# power_measure.net
KiCad netlist of a schematic drawn in Altium Designer
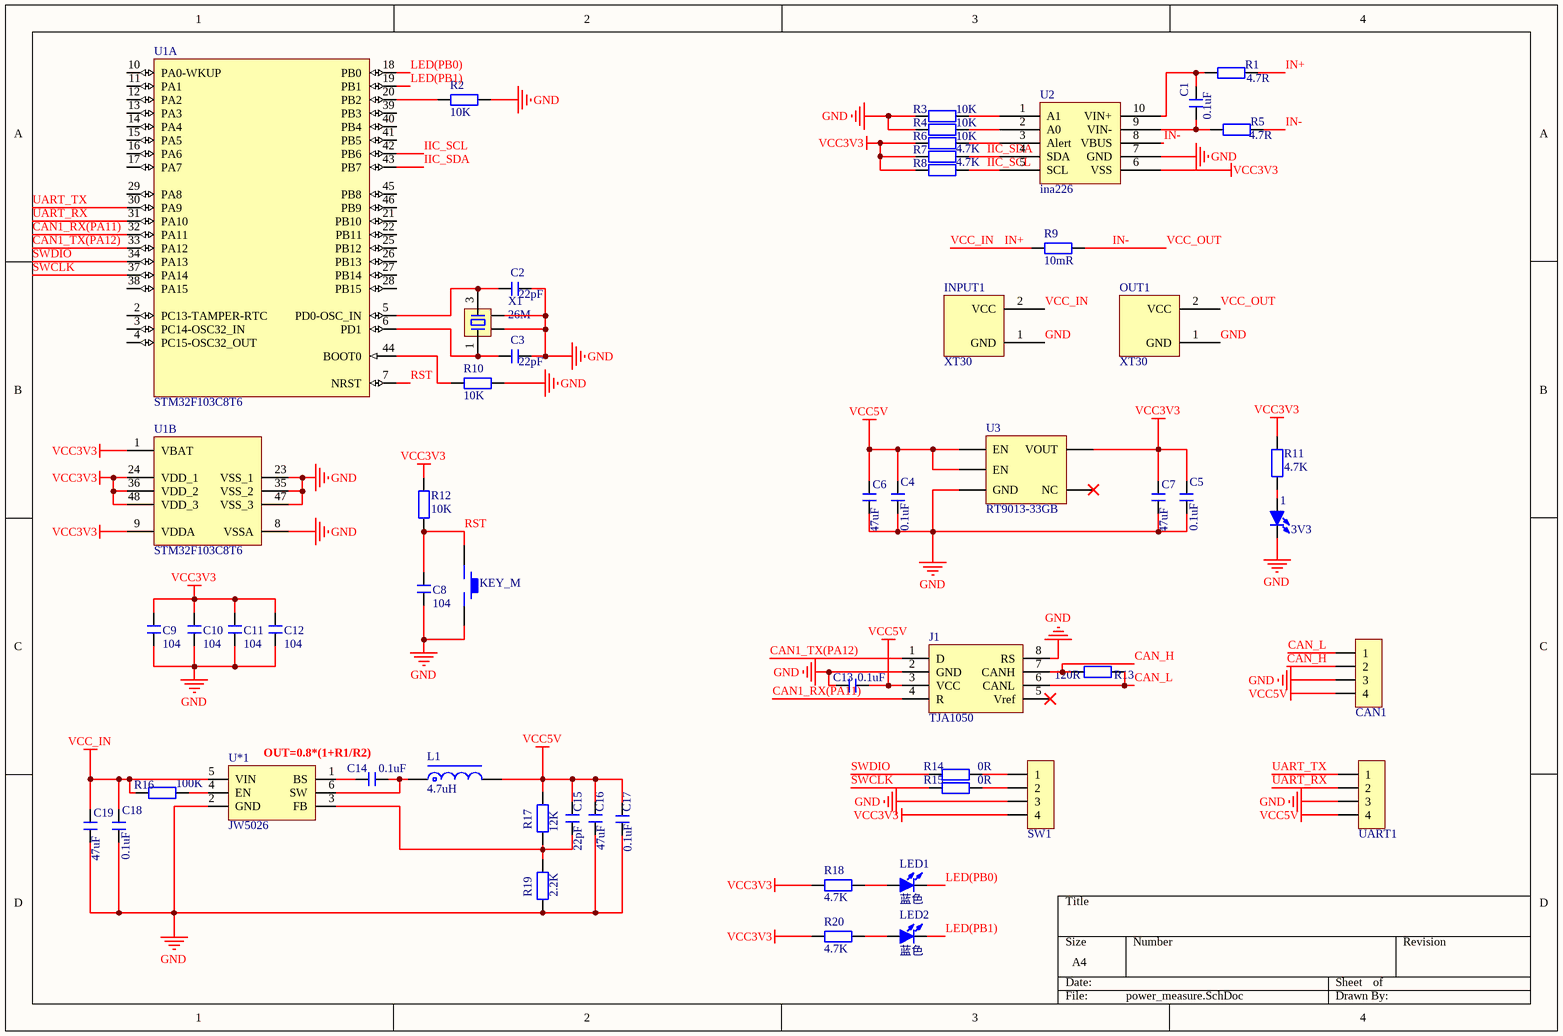
[diagram p0: power_measure.SchDoc]

(export (version "E")
  (design (tool "Eeschema 10.0.6"))
  (components
    (comp (ref "1")
      (value "3V3")
      (footprint "LED 0805R")
      (description "贴片LED")
      (libsource (lib "0.3 - LED发光二极管") (part "LED-SMD"))
    )
    (comp (ref "C1")
      (value "0.1uF")
      (footprint "C 0603_L")
      (description "贴片电容")
      (libsource (lib "0.1 - 电阻-电容-电感") (part "C"))
    )
    (comp (ref "C2")
      (value "22pF")
      (footprint "C 0603_L")
      (description "贴片电容")
      (libsource (lib "0.1 - 电阻-电容-电感") (part "C"))
    )
    (comp (ref "C3")
      (value "22pF")
      (footprint "C 0603_L")
      (description "贴片电容")
      (libsource (lib "0.1 - 电阻-电容-电感") (part "C"))
    )
    (comp (ref "C4")
      (value "0.1uF")
      (footprint "C 0805_L")
      (description "贴片电容")
      (libsource (lib "0.1 - 电阻-电容-电感") (part "C"))
    )
    (comp (ref "C5")
      (value "0.1uF")
      (footprint "C 0805_L")
      (description "贴片电容")
      (libsource (lib "0.1 - 电阻-电容-电感") (part "C"))
    )
    (comp (ref "C6")
      (value "47uF")
      (footprint "C 0805_L")
      (description "贴片电容")
      (libsource (lib "0.1 - 电阻-电容-电感") (part "C"))
    )
    (comp (ref "C7")
      (value "47uF")
      (footprint "C 0805_L")
      (description "贴片电容")
      (libsource (lib "0.1 - 电阻-电容-电感") (part "C"))
    )
    (comp (ref "C8")
      (value "104")
      (footprint "C 0603_L")
      (description "贴片电容")
      (libsource (lib "0.1 - 电阻-电容-电感") (part "C"))
    )
    (comp (ref "C9")
      (value "104")
      (footprint "C 0603_L")
      (description "贴片电容")
      (libsource (lib "0.1 - 电阻-电容-电感") (part "C"))
    )
    (comp (ref "C10")
      (value "104")
      (footprint "C 0603_L")
      (description "贴片电容")
      (libsource (lib "0.1 - 电阻-电容-电感") (part "C"))
    )
    (comp (ref "C11")
      (value "104")
      (footprint "C 0603_L")
      (description "贴片电容")
      (libsource (lib "0.1 - 电阻-电容-电感") (part "C"))
    )
    (comp (ref "C12")
      (value "104")
      (footprint "C 0603_L")
      (description "贴片电容")
      (libsource (lib "0.1 - 电阻-电容-电感") (part "C"))
    )
    (comp (ref "C13")
      (value "0.1uF")
      (footprint "C 0603_L")
      (description "贴片电容")
      (libsource (lib "0.1 - 电阻-电容-电感") (part "C"))
    )
    (comp (ref "C14")
      (value "0.1uF")
      (footprint "C 0603_L")
      (description "贴片电容")
      (libsource (lib "0.1 - 电阻-电容-电感") (part "C"))
    )
    (comp (ref "C15")
      (value "22pF")
      (footprint "C 0603_L")
      (description "贴片电容")
      (libsource (lib "0.1 - 电阻-电容-电感") (part "C"))
    )
    (comp (ref "C16")
      (value "47uF")
      (footprint "C 0805_L")
      (description "贴片电容")
      (libsource (lib "0.1 - 电阻-电容-电感") (part "C"))
    )
    (comp (ref "C17")
      (value "0.1uF")
      (footprint "C 0805_L")
      (description "贴片电容")
      (libsource (lib "0.1 - 电阻-电容-电感") (part "C"))
    )
    (comp (ref "C18")
      (value "0.1uF")
      (footprint "C 0805_L")
      (description "贴片电容")
      (libsource (lib "0.1 - 电阻-电容-电感") (part "C"))
    )
    (comp (ref "C19")
      (value "47uF")
      (footprint "C 0805_L")
      (description "贴片电容")
      (libsource (lib "0.1 - 电阻-电容-电感") (part "C"))
    )
    (comp (ref "CAN1")
      (value "HDR-1X4")
      (footprint "MX 1.25-WS-4P")
      (description "4P接插件")
      (libsource (lib "5.0 - 接插件-脚距1.25") (part "Header 4"))
    )
    (comp (ref "INPUT1")
      (value "XT30")
      (footprint "mx_pcb_library:XT30PW-M")
      (libsource (lib "mx_pcb_library") (part "XT30"))
    )
    (comp (ref "J1")
      (value "TJA1050")
      (footprint "mx_pcb_library:SOIC-8_150mil")
      (description "CAN芯片")
      (libsource (lib "mx_pcb_library") (part "TJA1050"))
    )
    (comp (ref "L1")
      (value "4.7uH")
      (footprint "CD53")
      (description "CD系列贴片线绕功率电感")
      (libsource (lib "0.1 - 电阻-电容-电感") (part "L-SMD"))
    )
    (comp (ref "LED1")
      (value "蓝色")
      (footprint "LED 0805B")
      (description "贴片LED")
      (libsource (lib "0.3 - LED发光二极管") (part "LED-SMD"))
    )
    (comp (ref "LED2")
      (value "蓝色")
      (footprint "LED 0805B")
      (description "贴片LED")
      (libsource (lib "0.3 - LED发光二极管") (part "LED-SMD"))
    )
    (comp (ref "OUT1")
      (value "XT30")
      (footprint "mx_pcb_library:XT30PW-F")
      (libsource (lib "mx_pcb_library") (part "XT30"))
    )
    (comp (ref "R1")
      (value "4.7R")
      (footprint "R 0603_L")
      (description "贴片电阻")
      (libsource (lib "0.1 - 电阻-电容-电感") (part "R"))
    )
    (comp (ref "R2")
      (value "10K")
      (footprint "R 0603_L")
      (description "贴片电阻")
      (libsource (lib "0.1 - 电阻-电容-电感") (part "R"))
    )
    (comp (ref "R3")
      (value "10K")
      (footprint "R 0603_L")
      (description "贴片电阻")
      (libsource (lib "0.1 - 电阻-电容-电感") (part "R"))
    )
    (comp (ref "R4")
      (value "10K")
      (footprint "R 0603_L")
      (description "贴片电阻")
      (libsource (lib "0.1 - 电阻-电容-电感") (part "R"))
    )
    (comp (ref "R5")
      (value "4.7R")
      (footprint "R 0603_L")
      (description "贴片电阻")
      (libsource (lib "0.1 - 电阻-电容-电感") (part "R"))
    )
    (comp (ref "R6")
      (value "10K")
      (footprint "R 0603_L")
      (description "贴片电阻")
      (libsource (lib "0.1 - 电阻-电容-电感") (part "R"))
    )
    (comp (ref "R7")
      (value "4.7K")
      (footprint "R 0603_L")
      (description "贴片电阻")
      (libsource (lib "0.1 - 电阻-电容-电感") (part "R"))
    )
    (comp (ref "R8")
      (value "4.7K")
      (footprint "R 0603_L")
      (description "贴片电阻")
      (libsource (lib "0.1 - 电阻-电容-电感") (part "R"))
    )
    (comp (ref "R9")
      (value "10mR")
      (footprint "R 2512_M")
      (description "贴片电阻")
      (libsource (lib "0.1 - 电阻-电容-电感") (part "R"))
    )
    (comp (ref "R10")
      (value "10K")
      (footprint "R 0603_L")
      (description "贴片电阻")
      (libsource (lib "0.1 - 电阻-电容-电感") (part "R"))
    )
    (comp (ref "R11")
      (value "4.7K")
      (footprint "R 0603_L")
      (description "贴片电阻")
      (libsource (lib "0.1 - 电阻-电容-电感") (part "R"))
    )
    (comp (ref "R12")
      (value "10K")
      (footprint "R 0603_L")
      (description "贴片电阻")
      (libsource (lib "0.1 - 电阻-电容-电感") (part "R"))
    )
    (comp (ref "R13")
      (value "120R")
      (footprint "R 0603_L")
      (description "贴片电阻")
      (libsource (lib "0.1 - 电阻-电容-电感") (part "R"))
    )
    (comp (ref "R14")
      (value "0R")
      (footprint "R 0603_L")
      (description "贴片电阻")
      (libsource (lib "0.1 - 电阻-电容-电感") (part "R"))
    )
    (comp (ref "R15")
      (value "0R")
      (footprint "R 0603_L")
      (description "贴片电阻")
      (libsource (lib "0.1 - 电阻-电容-电感") (part "R"))
    )
    (comp (ref "R16")
      (value "100K")
      (footprint "R 0603_L")
      (description "贴片电阻")
      (libsource (lib "0.1 - 电阻-电容-电感") (part "R"))
    )
    (comp (ref "R17")
      (value "12K")
      (footprint "R 0603_L")
      (description "贴片电阻")
      (libsource (lib "0.1 - 电阻-电容-电感") (part "R"))
    )
    (comp (ref "R18")
      (value "4.7K")
      (footprint "R 0603_L")
      (description "贴片电阻")
      (libsource (lib "0.1 - 电阻-电容-电感") (part "R"))
    )
    (comp (ref "R19")
      (value "2.2K")
      (footprint "R 0603_L")
      (description "贴片电阻")
      (libsource (lib "0.1 - 电阻-电容-电感") (part "R"))
    )
    (comp (ref "R20")
      (value "4.7K")
      (footprint "R 0603_L")
      (description "贴片电阻")
      (libsource (lib "0.1 - 电阻-电容-电感") (part "R"))
    )
    (comp (ref "RST1")
      (value "KEY_M")
      (footprint "mx_pcb_library:SMD-3.2*4.2")
      (libsource (lib "mx_pcb_library") (part "KEY_M"))
    )
    (comp (ref "SW1")
      (value "HDR-1X4")
      (footprint "MX 1.25-WS-4P")
      (description "4P接插件")
      (libsource (lib "5.0 - 接插件-脚距1.25") (part "Header 4"))
    )
    (comp (ref "U*1")
      (value "JW5026")
      (footprint "SOT-23-6_L2.9-W1.6-P0.95-LS2.8-BL")
      (description "BUCK、MAX40V")
      (libsource (lib "mx_pcb_library") (part "JW5026"))
    )
    (comp (ref "U1")
      (value "STM32F103C8T6")
      (footprint "LQFP48_N")
      (libsource (lib "2.3 - STM32 F1系列MCU 集成库") (part "STM32F103C8T6"))
    )
    (comp (ref "U2")
      (value "ina226")
      (footprint "mx_pcb_library:MSOP-10")
      (libsource (lib "mx_pcb_library") (part "INA226"))
    )
    (comp (ref "U3")
      (value "RT9013-33GB")
      (footprint "SOT23-5M")
      (libsource (lib "mx_pcb_library") (part "RT9013-33GB"))
    )
    (comp (ref "UART1")
      (value "HDR-1X4")
      (footprint "MX 1.25-WS-4P")
      (description "4P接插件")
      (libsource (lib "5.0 - 接插件-脚距1.25") (part "Header 4"))
    )
    (comp (ref "X1")
      (value "26M")
      (footprint "OSC 3225-4P")
      (description "4脚无源晶振")
      (libsource (lib "2.0 - 保险丝-晶振-光耦") (part "XTAL-4P"))
    )
  )
  (nets
    (net (code "1") (name "/CAN1_RX(PA11)") (class "Default")
      (node (ref "J1") (pin "4") (pinfunction "R_4") (pintype "passive"))
      (node (ref "U1") (pin "32") (pinfunction "PA11_32") (pintype "bidirectional"))
    )
    (net (code "2") (name "/CAN1_TX(PA12)") (class "Default")
      (node (ref "J1") (pin "1") (pinfunction "D_1") (pintype "passive"))
      (node (ref "U1") (pin "33") (pinfunction "PA12_33") (pintype "bidirectional"))
    )
    (net (code "3") (name "/CAN_H") (class "Default")
      (node (ref "CAN1") (pin "2") (pinfunction "2_2") (pintype "passive"))
      (node (ref "J1") (pin "7") (pinfunction "CANH_7") (pintype "passive"))
      (node (ref "R13") (pin "1") (pinfunction "1_1") (pintype "passive"))
    )
    (net (code "4") (name "/CAN_L") (class "Default")
      (node (ref "CAN1") (pin "1") (pinfunction "1_1") (pintype "passive"))
      (node (ref "J1") (pin "6") (pinfunction "CANL_6") (pintype "passive"))
      (node (ref "R13") (pin "2") (pinfunction "2_2") (pintype "passive"))
    )
    (net (code "5") (name "/IIC_SCL") (class "Default")
      (node (ref "R8") (pin "1") (pinfunction "1_1") (pintype "passive"))
      (node (ref "U1") (pin "42") (pinfunction "PB6_42") (pintype "bidirectional"))
      (node (ref "U2") (pin "5") (pinfunction "SCL_5") (pintype "passive"))
    )
    (net (code "6") (name "/IIC_SDA") (class "Default")
      (node (ref "R7") (pin "1") (pinfunction "1_1") (pintype "passive"))
      (node (ref "U1") (pin "43") (pinfunction "PB7_43") (pintype "bidirectional"))
      (node (ref "U2") (pin "4") (pinfunction "SDA_4") (pintype "passive"))
    )
    (net (code "7") (name "/IN-") (class "Default")
      (node (ref "OUT1") (pin "2") (pinfunction "VCC_2") (pintype "passive"))
      (node (ref "R5") (pin "2") (pinfunction "2_2") (pintype "passive"))
      (node (ref "R9") (pin "2") (pinfunction "2_2") (pintype "passive"))
      (node (ref "U2") (pin "8") (pinfunction "VBUS_8") (pintype "passive"))
    )
    (net (code "8") (name "/LED(PB0)") (class "Default")
      (node (ref "LED1") (pin "2") (pinfunction "K_2") (pintype "passive"))
      (node (ref "U1") (pin "18") (pinfunction "PB0_18") (pintype "bidirectional"))
    )
    (net (code "9") (name "/LED(PB1)") (class "Default")
      (node (ref "LED2") (pin "2") (pinfunction "K_2") (pintype "passive"))
      (node (ref "U1") (pin "19") (pinfunction "PB1_19") (pintype "bidirectional"))
    )
    (net (code "10") (name "/RST") (class "Default")
      (node (ref "C8") (pin "2") (pinfunction "2_2") (pintype "passive"))
      (node (ref "R12") (pin "1") (pinfunction "1_1") (pintype "passive"))
      (node (ref "RST1") (pin "1") (pinfunction "1_1") (pintype "passive"))
      (node (ref "U1") (pin "7") (pinfunction "NRST_7") (pintype "bidirectional"))
    )
    (net (code "11") (name "/SWCLK") (class "Default")
      (node (ref "R15") (pin "1") (pinfunction "1_1") (pintype "passive"))
      (node (ref "U1") (pin "37") (pinfunction "PA14_37") (pintype "bidirectional"))
    )
    (net (code "12") (name "/SWDIO") (class "Default")
      (node (ref "R14") (pin "1") (pinfunction "1_1") (pintype "passive"))
      (node (ref "U1") (pin "34") (pinfunction "PA13_34") (pintype "bidirectional"))
    )
    (net (code "13") (name "/UART_RX") (class "Default")
      (node (ref "U1") (pin "31") (pinfunction "PA10_31") (pintype "bidirectional"))
      (node (ref "UART1") (pin "2") (pinfunction "2_2") (pintype "passive"))
    )
    (net (code "14") (name "/UART_TX") (class "Default")
      (node (ref "U1") (pin "30") (pinfunction "PA9_30") (pintype "bidirectional"))
      (node (ref "UART1") (pin "1") (pinfunction "1_1") (pintype "passive"))
    )
    (net (code "15") (name "GND") (class "Default")
      (node (ref "1") (pin "2") (pinfunction "K_2") (pintype "passive"))
      (node (ref "C10") (pin "1") (pinfunction "1_1") (pintype "passive"))
      (node (ref "C11") (pin "1") (pinfunction "1_1") (pintype "passive"))
      (node (ref "C12") (pin "1") (pinfunction "1_1") (pintype "passive"))
      (node (ref "C13") (pin "2") (pinfunction "2_2") (pintype "passive"))
      (node (ref "C16") (pin "1") (pinfunction "1_1") (pintype "passive"))
      (node (ref "C17") (pin "1") (pinfunction "1_1") (pintype "passive"))
      (node (ref "C18") (pin "1") (pinfunction "1_1") (pintype "passive"))
      (node (ref "C19") (pin "1") (pinfunction "1_1") (pintype "passive"))
      (node (ref "C2") (pin "2") (pinfunction "2_2") (pintype "passive"))
      (node (ref "C3") (pin "2") (pinfunction "2_2") (pintype "passive"))
      (node (ref "C4") (pin "1") (pinfunction "1_1") (pintype "passive"))
      (node (ref "C5") (pin "1") (pinfunction "1_1") (pintype "passive"))
      (node (ref "C6") (pin "1") (pinfunction "1_1") (pintype "passive"))
      (node (ref "C7") (pin "1") (pinfunction "1_1") (pintype "passive"))
      (node (ref "C8") (pin "1") (pinfunction "1_1") (pintype "passive"))
      (node (ref "C9") (pin "1") (pinfunction "1_1") (pintype "passive"))
      (node (ref "CAN1") (pin "3") (pinfunction "3_3") (pintype "passive"))
      (node (ref "INPUT1") (pin "1") (pinfunction "GND_1") (pintype "passive"))
      (node (ref "J1") (pin "2") (pinfunction "GND_2") (pintype "passive"))
      (node (ref "J1") (pin "8") (pinfunction "RS_8") (pintype "passive"))
      (node (ref "OUT1") (pin "1") (pinfunction "GND_1") (pintype "passive"))
      (node (ref "R10") (pin "2") (pinfunction "2_2") (pintype "passive"))
      (node (ref "R19") (pin "1") (pinfunction "1_1") (pintype "passive"))
      (node (ref "R2") (pin "2") (pinfunction "2_2") (pintype "passive"))
      (node (ref "R3") (pin "2") (pinfunction "2_2") (pintype "passive"))
      (node (ref "R4") (pin "2") (pinfunction "2_2") (pintype "passive"))
      (node (ref "RST1") (pin "2") (pinfunction "2_2") (pintype "passive"))
      (node (ref "SW1") (pin "3") (pinfunction "3_3") (pintype "passive"))
      (node (ref "U*1") (pin "2") (pinfunction "GND_2") (pintype "passive"))
      (node (ref "U1") (pin "23") (pinfunction "VSS_1_23") (pintype "power_in"))
      (node (ref "U1") (pin "35") (pinfunction "VSS_2_35") (pintype "power_in"))
      (node (ref "U1") (pin "47") (pinfunction "VSS_3_47") (pintype "power_in"))
      (node (ref "U1") (pin "8") (pinfunction "VSSA_8") (pintype "power_in"))
      (node (ref "U2") (pin "7") (pinfunction "GND_7") (pintype "passive"))
      (node (ref "U3") (pin "2") (pinfunction "GND_2") (pintype "passive"))
      (node (ref "UART1") (pin "3") (pinfunction "3_3") (pintype "passive"))
      (node (ref "X1") (pin "2") (pinfunction "2_2") (pintype "passive"))
      (node (ref "X1") (pin "4") (pinfunction "4_4") (pintype "passive"))
    )
    (net (code "16") (name "Net-(1-A)") (class "Default")
      (node (ref "1") (pin "1") (pinfunction "A_1") (pintype "passive"))
      (node (ref "R11") (pin "2") (pinfunction "2_2") (pintype "passive"))
    )
    (net (code "17") (name "Net-(LED1-A)") (class "Default")
      (node (ref "LED1") (pin "1") (pinfunction "A_1") (pintype "passive"))
      (node (ref "R18") (pin "2") (pinfunction "2_2") (pintype "passive"))
    )
    (net (code "18") (name "Net-(LED2-A)") (class "Default")
      (node (ref "LED2") (pin "1") (pinfunction "A_1") (pintype "passive"))
      (node (ref "R20") (pin "2") (pinfunction "2_2") (pintype "passive"))
    )
    (net (code "19") (name "Net-(R14-Pad2)") (class "Default")
      (node (ref "R14") (pin "2") (pinfunction "2_2") (pintype "passive"))
      (node (ref "SW1") (pin "1") (pinfunction "1_1") (pintype "passive"))
    )
    (net (code "20") (name "Net-(R15-Pad2)") (class "Default")
      (node (ref "R15") (pin "2") (pinfunction "2_2") (pintype "passive"))
      (node (ref "SW1") (pin "2") (pinfunction "2_2") (pintype "passive"))
    )
    (net (code "21") (name "Net-(U*1-BS)") (class "Default")
      (node (ref "C14") (pin "1") (pinfunction "1_1") (pintype "passive"))
      (node (ref "U*1") (pin "1") (pinfunction "BS_1") (pintype "passive"))
    )
    (net (code "22") (name "Net-(U*1-EN)") (class "Default")
      (node (ref "R16") (pin "1") (pinfunction "1_1") (pintype "passive"))
      (node (ref "U*1") (pin "4") (pinfunction "EN_4") (pintype "passive"))
    )
    (net (code "23") (name "Net-(U*1-FB)") (class "Default")
      (node (ref "C15") (pin "1") (pinfunction "1_1") (pintype "passive"))
      (node (ref "R17") (pin "1") (pinfunction "1_1") (pintype "passive"))
      (node (ref "R19") (pin "2") (pinfunction "2_2") (pintype "passive"))
      (node (ref "U*1") (pin "3") (pinfunction "FB_3") (pintype "passive"))
    )
    (net (code "24") (name "Net-(U*1-SW)") (class "Default")
      (node (ref "C14") (pin "2") (pinfunction "2_2") (pintype "passive"))
      (node (ref "L1") (pin "1") (pinfunction "1_1") (pintype "passive"))
      (node (ref "U*1") (pin "6") (pinfunction "SW_6") (pintype "passive"))
    )
    (net (code "25") (name "Net-(U1A-BOOT0)") (class "Default")
      (node (ref "R10") (pin "1") (pinfunction "1_1") (pintype "passive"))
      (node (ref "U1") (pin "44") (pinfunction "BOOT0_44") (pintype "input"))
    )
    (net (code "26") (name "Net-(U1A-PB2)") (class "Default")
      (node (ref "R2") (pin "1") (pinfunction "1_1") (pintype "passive"))
      (node (ref "U1") (pin "20") (pinfunction "PB2_20") (pintype "bidirectional"))
    )
    (net (code "27") (name "Net-(U1A-PD0-OSC_IN)") (class "Default")
      (node (ref "C2") (pin "1") (pinfunction "1_1") (pintype "passive"))
      (node (ref "U1") (pin "5") (pinfunction "PD0-OSC_IN_5") (pintype "bidirectional"))
      (node (ref "X1") (pin "3") (pinfunction "3_3") (pintype "passive"))
    )
    (net (code "28") (name "Net-(U1A-PD1)") (class "Default")
      (node (ref "C3") (pin "1") (pinfunction "1_1") (pintype "passive"))
      (node (ref "U1") (pin "6") (pinfunction "PD1_6") (pintype "bidirectional"))
      (node (ref "X1") (pin "1") (pinfunction "1_1") (pintype "passive"))
    )
    (net (code "29") (name "Net-(U2-A0)") (class "Default")
      (node (ref "R4") (pin "1") (pinfunction "1_1") (pintype "passive"))
      (node (ref "U2") (pin "2") (pinfunction "A0_2") (pintype "passive"))
    )
    (net (code "30") (name "Net-(U2-A1)") (class "Default")
      (node (ref "R3") (pin "1") (pinfunction "1_1") (pintype "passive"))
      (node (ref "U2") (pin "1") (pinfunction "A1_1") (pintype "passive"))
    )
    (net (code "31") (name "Net-(U2-Alert)") (class "Default")
      (node (ref "R6") (pin "1") (pinfunction "1_1") (pintype "passive"))
      (node (ref "U2") (pin "3") (pinfunction "Alert_3") (pintype "passive"))
    )
    (net (code "32") (name "Net-(U2-VIN+)") (class "Default")
      (node (ref "C1") (pin "2") (pinfunction "2_2") (pintype "passive"))
      (node (ref "R1") (pin "1") (pinfunction "1_1") (pintype "passive"))
      (node (ref "U2") (pin "10") (pinfunction "VIN+_10") (pintype "passive"))
    )
    (net (code "33") (name "Net-(U2-VIN-)") (class "Default")
      (node (ref "C1") (pin "1") (pinfunction "1_1") (pintype "passive"))
      (node (ref "R5") (pin "1") (pinfunction "1_1") (pintype "passive"))
      (node (ref "U2") (pin "9") (pinfunction "VIN-_9") (pintype "passive"))
    )
    (net (code "34") (name "VCC3V3") (class "Default")
      (node (ref "C10") (pin "2") (pinfunction "2_2") (pintype "passive"))
      (node (ref "C11") (pin "2") (pinfunction "2_2") (pintype "passive"))
      (node (ref "C12") (pin "2") (pinfunction "2_2") (pintype "passive"))
      (node (ref "C5") (pin "2") (pinfunction "2_2") (pintype "passive"))
      (node (ref "C7") (pin "2") (pinfunction "2_2") (pintype "passive"))
      (node (ref "C9") (pin "2") (pinfunction "2_2") (pintype "passive"))
      (node (ref "R11") (pin "1") (pinfunction "1_1") (pintype "passive"))
      (node (ref "R12") (pin "2") (pinfunction "2_2") (pintype "passive"))
      (node (ref "R18") (pin "1") (pinfunction "1_1") (pintype "passive"))
      (node (ref "R20") (pin "1") (pinfunction "1_1") (pintype "passive"))
      (node (ref "R6") (pin "2") (pinfunction "2_2") (pintype "passive"))
      (node (ref "R7") (pin "2") (pinfunction "2_2") (pintype "passive"))
      (node (ref "R8") (pin "2") (pinfunction "2_2") (pintype "passive"))
      (node (ref "SW1") (pin "4") (pinfunction "4_4") (pintype "passive"))
      (node (ref "U1") (pin "1") (pinfunction "VBAT_1") (pintype "power_in"))
      (node (ref "U1") (pin "24") (pinfunction "VDD_1_24") (pintype "power_in"))
      (node (ref "U1") (pin "36") (pinfunction "VDD_2_36") (pintype "power_in"))
      (node (ref "U1") (pin "48") (pinfunction "VDD_3_48") (pintype "power_in"))
      (node (ref "U1") (pin "9") (pinfunction "VDDA_9") (pintype "power_in"))
      (node (ref "U2") (pin "6") (pinfunction "VSS_6") (pintype "passive"))
      (node (ref "U3") (pin "5") (pinfunction "VOUT_5") (pintype "passive"))
    )
    (net (code "35") (name "VCC5V") (class "Default")
      (node (ref "C13") (pin "1") (pinfunction "1_1") (pintype "passive"))
      (node (ref "C15") (pin "2") (pinfunction "2_2") (pintype "passive"))
      (node (ref "C16") (pin "2") (pinfunction "2_2") (pintype "passive"))
      (node (ref "C17") (pin "2") (pinfunction "2_2") (pintype "passive"))
      (node (ref "C4") (pin "2") (pinfunction "2_2") (pintype "passive"))
      (node (ref "C6") (pin "2") (pinfunction "2_2") (pintype "passive"))
      (node (ref "CAN1") (pin "4") (pinfunction "4_4") (pintype "passive"))
      (node (ref "J1") (pin "3") (pinfunction "VCC_3") (pintype "passive"))
      (node (ref "L1") (pin "2") (pinfunction "2_2") (pintype "passive"))
      (node (ref "R17") (pin "2") (pinfunction "2_2") (pintype "passive"))
      (node (ref "U3") (pin "1") (pinfunction "EN_1") (pintype "passive"))
      (node (ref "U3") (pin "3") (pinfunction "EN_3") (pintype "passive"))
      (node (ref "UART1") (pin "4") (pinfunction "4_4") (pintype "passive"))
    )
    (net (code "36") (name "VCC_IN") (class "Default")
      (node (ref "C18") (pin "2") (pinfunction "2_2") (pintype "passive"))
      (node (ref "C19") (pin "2") (pinfunction "2_2") (pintype "passive"))
      (node (ref "INPUT1") (pin "2") (pinfunction "VCC_2") (pintype "passive"))
      (node (ref "R1") (pin "2") (pinfunction "2_2") (pintype "passive"))
      (node (ref "R16") (pin "2") (pinfunction "2_2") (pintype "passive"))
      (node (ref "R9") (pin "1") (pinfunction "1_1") (pintype "passive"))
      (node (ref "U*1") (pin "5") (pinfunction "VIN_5") (pintype "passive"))
    )
    (net (code "37") (name "unconnected-(J1-Vref-Pad5)") (class "Default")
      (node (ref "J1") (pin "5") (pinfunction "Vref_5") (pintype "passive+no_connect"))
    )
    (net (code "38") (name "unconnected-(U1A-PA0-WKUP-Pad10)") (class "Default")
      (node (ref "U1") (pin "10") (pinfunction "PA0-WKUP_10") (pintype "bidirectional"))
    )
    (net (code "39") (name "unconnected-(U1A-PA1-Pad11)") (class "Default")
      (node (ref "U1") (pin "11") (pinfunction "PA1_11") (pintype "bidirectional"))
    )
    (net (code "40") (name "unconnected-(U1A-PA2-Pad12)") (class "Default")
      (node (ref "U1") (pin "12") (pinfunction "PA2_12") (pintype "bidirectional"))
    )
    (net (code "41") (name "unconnected-(U1A-PA3-Pad13)") (class "Default")
      (node (ref "U1") (pin "13") (pinfunction "PA3_13") (pintype "bidirectional"))
    )
    (net (code "42") (name "unconnected-(U1A-PA4-Pad14)") (class "Default")
      (node (ref "U1") (pin "14") (pinfunction "PA4_14") (pintype "bidirectional"))
    )
    (net (code "43") (name "unconnected-(U1A-PA5-Pad15)") (class "Default")
      (node (ref "U1") (pin "15") (pinfunction "PA5_15") (pintype "bidirectional"))
    )
    (net (code "44") (name "unconnected-(U1A-PA6-Pad16)") (class "Default")
      (node (ref "U1") (pin "16") (pinfunction "PA6_16") (pintype "bidirectional"))
    )
    (net (code "45") (name "unconnected-(U1A-PA7-Pad17)") (class "Default")
      (node (ref "U1") (pin "17") (pinfunction "PA7_17") (pintype "bidirectional"))
    )
    (net (code "46") (name "unconnected-(U1A-PA8-Pad29)") (class "Default")
      (node (ref "U1") (pin "29") (pinfunction "PA8_29") (pintype "bidirectional"))
    )
    (net (code "47") (name "unconnected-(U1A-PA15-Pad38)") (class "Default")
      (node (ref "U1") (pin "38") (pinfunction "PA15_38") (pintype "bidirectional"))
    )
    (net (code "48") (name "unconnected-(U1A-PB3-Pad39)") (class "Default")
      (node (ref "U1") (pin "39") (pinfunction "PB3_39") (pintype "bidirectional"))
    )
    (net (code "49") (name "unconnected-(U1A-PB4-Pad40)") (class "Default")
      (node (ref "U1") (pin "40") (pinfunction "PB4_40") (pintype "bidirectional"))
    )
    (net (code "50") (name "unconnected-(U1A-PB5-Pad41)") (class "Default")
      (node (ref "U1") (pin "41") (pinfunction "PB5_41") (pintype "bidirectional"))
    )
    (net (code "51") (name "unconnected-(U1A-PB8-Pad45)") (class "Default")
      (node (ref "U1") (pin "45") (pinfunction "PB8_45") (pintype "bidirectional"))
    )
    (net (code "52") (name "unconnected-(U1A-PB9-Pad46)") (class "Default")
      (node (ref "U1") (pin "46") (pinfunction "PB9_46") (pintype "bidirectional"))
    )
    (net (code "53") (name "unconnected-(U1A-PB10-Pad21)") (class "Default")
      (node (ref "U1") (pin "21") (pinfunction "PB10_21") (pintype "bidirectional"))
    )
    (net (code "54") (name "unconnected-(U1A-PB11-Pad22)") (class "Default")
      (node (ref "U1") (pin "22") (pinfunction "PB11_22") (pintype "bidirectional"))
    )
    (net (code "55") (name "unconnected-(U1A-PB12-Pad25)") (class "Default")
      (node (ref "U1") (pin "25") (pinfunction "PB12_25") (pintype "bidirectional"))
    )
    (net (code "56") (name "unconnected-(U1A-PB13-Pad26)") (class "Default")
      (node (ref "U1") (pin "26") (pinfunction "PB13_26") (pintype "bidirectional"))
    )
    (net (code "57") (name "unconnected-(U1A-PB14-Pad27)") (class "Default")
      (node (ref "U1") (pin "27") (pinfunction "PB14_27") (pintype "bidirectional"))
    )
    (net (code "58") (name "unconnected-(U1A-PB15-Pad28)") (class "Default")
      (node (ref "U1") (pin "28") (pinfunction "PB15_28") (pintype "bidirectional"))
    )
    (net (code "59") (name "unconnected-(U1A-PC13-TAMPER-RTC-Pad2)") (class "Default")
      (node (ref "U1") (pin "2") (pinfunction "PC13-TAMPER-RTC_2") (pintype "bidirectional"))
    )
    (net (code "60") (name "unconnected-(U1A-PC14-OSC32_IN-Pad3)") (class "Default")
      (node (ref "U1") (pin "3") (pinfunction "PC14-OSC32_IN_3") (pintype "bidirectional"))
    )
    (net (code "61") (name "unconnected-(U1A-PC15-OSC32_OUT-Pad4)") (class "Default")
      (node (ref "U1") (pin "4") (pinfunction "PC15-OSC32_OUT_4") (pintype "bidirectional"))
    )
    (net (code "62") (name "unconnected-(U3-NC-Pad4)") (class "Default")
      (node (ref "U3") (pin "4") (pinfunction "NC_4") (pintype "passive+no_connect"))
    )
  )
)
